# LevelShifter.net
KiCad netlist of a schematic drawn in Altium Designer
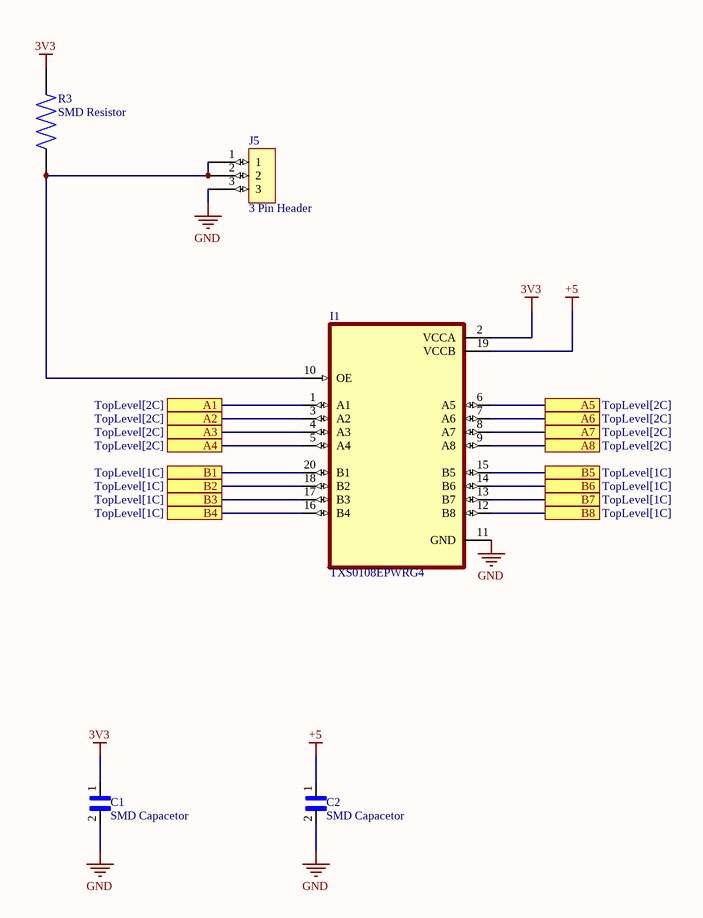
[diagram p0: LevelShifter.SchDoc]

(export (version "E")
  (design (tool "Eeschema 10.0.6"))
  (components
    (comp (ref "C1")
      (value "SMD Capacetor")
      (footprint "SMD Capacetor-Footprint-1")
      (description "Generic SMD Capacetor")
      (libsource (lib "Tobias") (part "SMD Capacetor-Symbol-1"))
    )
    (comp (ref "C2")
      (value "SMD Capacetor")
      (footprint "SMD Capacetor-Footprint-1")
      (description "Generic SMD Capacetor")
      (libsource (lib "Tobias") (part "SMD Capacetor-Symbol-1"))
    )
    (comp (ref "I1")
      (value "TXS0108EPWRG4")
      (footprint "TXS0108EPWRG4-Footprint-1")
      (description "8-bit bidirectional voltage-level shifter")
      (libsource (lib "Tobias") (part "TXS0108EPWRG4-Symbol-1"))
    )
    (comp (ref "J5")
      (value "3 Pin Header")
      (footprint "3 Pin Header-Footprint-1")
      (description "3 Pin Breakout Header")
      (libsource (lib "Tobias") (part "3 Pin Header-Symbol-1"))
    )
    (comp (ref "R3")
      (value "SMD Resistor")
      (footprint "SMD Resistor-Footprint-1")
      (description "Generic SMD Resistor")
      (libsource (lib "Tobias") (part "SMD Resistor-Symbol-1"))
    )
  )
  (nets
    (net (code "1") (name "+5") (class "Default")
      (node (ref "C2") (pin "1") (pinfunction "1_1") (pintype "passive"))
      (node (ref "I1") (pin "19") (pinfunction "VCCB_19") (pintype "power_in"))
    )
    (net (code "2") (name "/A1") (class "Default")
      (node (ref "I1") (pin "1") (pinfunction "A1_1") (pintype "bidirectional"))
    )
    (net (code "3") (name "/A2") (class "Default")
      (node (ref "I1") (pin "3") (pinfunction "A2_3") (pintype "bidirectional"))
    )
    (net (code "4") (name "/A3") (class "Default")
      (node (ref "I1") (pin "4") (pinfunction "A3_4") (pintype "bidirectional"))
    )
    (net (code "5") (name "/A4") (class "Default")
      (node (ref "I1") (pin "5") (pinfunction "A4_5") (pintype "bidirectional"))
    )
    (net (code "6") (name "/A5") (class "Default")
      (node (ref "I1") (pin "6") (pinfunction "A5_6") (pintype "bidirectional"))
    )
    (net (code "7") (name "/A6") (class "Default")
      (node (ref "I1") (pin "7") (pinfunction "A6_7") (pintype "bidirectional"))
    )
    (net (code "8") (name "/A7") (class "Default")
      (node (ref "I1") (pin "8") (pinfunction "A7_8") (pintype "bidirectional"))
    )
    (net (code "9") (name "/A8") (class "Default")
      (node (ref "I1") (pin "9") (pinfunction "A8_9") (pintype "bidirectional"))
    )
    (net (code "10") (name "/B1") (class "Default")
      (node (ref "I1") (pin "20") (pinfunction "B1_20") (pintype "bidirectional"))
    )
    (net (code "11") (name "/B2") (class "Default")
      (node (ref "I1") (pin "18") (pinfunction "B2_18") (pintype "bidirectional"))
    )
    (net (code "12") (name "/B3") (class "Default")
      (node (ref "I1") (pin "17") (pinfunction "B3_17") (pintype "bidirectional"))
    )
    (net (code "13") (name "/B4") (class "Default")
      (node (ref "I1") (pin "16") (pinfunction "B4_16") (pintype "bidirectional"))
    )
    (net (code "14") (name "/B5") (class "Default")
      (node (ref "I1") (pin "15") (pinfunction "B5_15") (pintype "bidirectional"))
    )
    (net (code "15") (name "/B6") (class "Default")
      (node (ref "I1") (pin "14") (pinfunction "B6_14") (pintype "bidirectional"))
    )
    (net (code "16") (name "/B7") (class "Default")
      (node (ref "I1") (pin "13") (pinfunction "B7_13") (pintype "bidirectional"))
    )
    (net (code "17") (name "/B8") (class "Default")
      (node (ref "I1") (pin "12") (pinfunction "B8_12") (pintype "bidirectional"))
    )
    (net (code "18") (name "3V3") (class "Default")
      (node (ref "C1") (pin "1") (pinfunction "1_1") (pintype "passive"))
      (node (ref "I1") (pin "2") (pinfunction "VCCA_2") (pintype "power_in"))
      (node (ref "R3") (pin "1") (pinfunction "1_1") (pintype "passive"))
    )
    (net (code "19") (name "GND") (class "Default")
      (node (ref "C1") (pin "2") (pinfunction "2_2") (pintype "passive"))
      (node (ref "C2") (pin "2") (pinfunction "2_2") (pintype "passive"))
      (node (ref "I1") (pin "11") (pinfunction "GND_11") (pintype "power_in"))
      (node (ref "J5") (pin "3") (pinfunction "3_3") (pintype "bidirectional"))
    )
    (net (code "20") (name "Net-(I1-OE)") (class "Default")
      (node (ref "I1") (pin "10") (pinfunction "OE_10") (pintype "input"))
      (node (ref "J5") (pin "1") (pinfunction "1_1") (pintype "bidirectional"))
      (node (ref "J5") (pin "2") (pinfunction "2_2") (pintype "bidirectional"))
      (node (ref "R3") (pin "2") (pinfunction "2_2") (pintype "passive"))
    )
  )
)
